# Backplane.net
KiCad netlist of a schematic drawn in Altium Designer
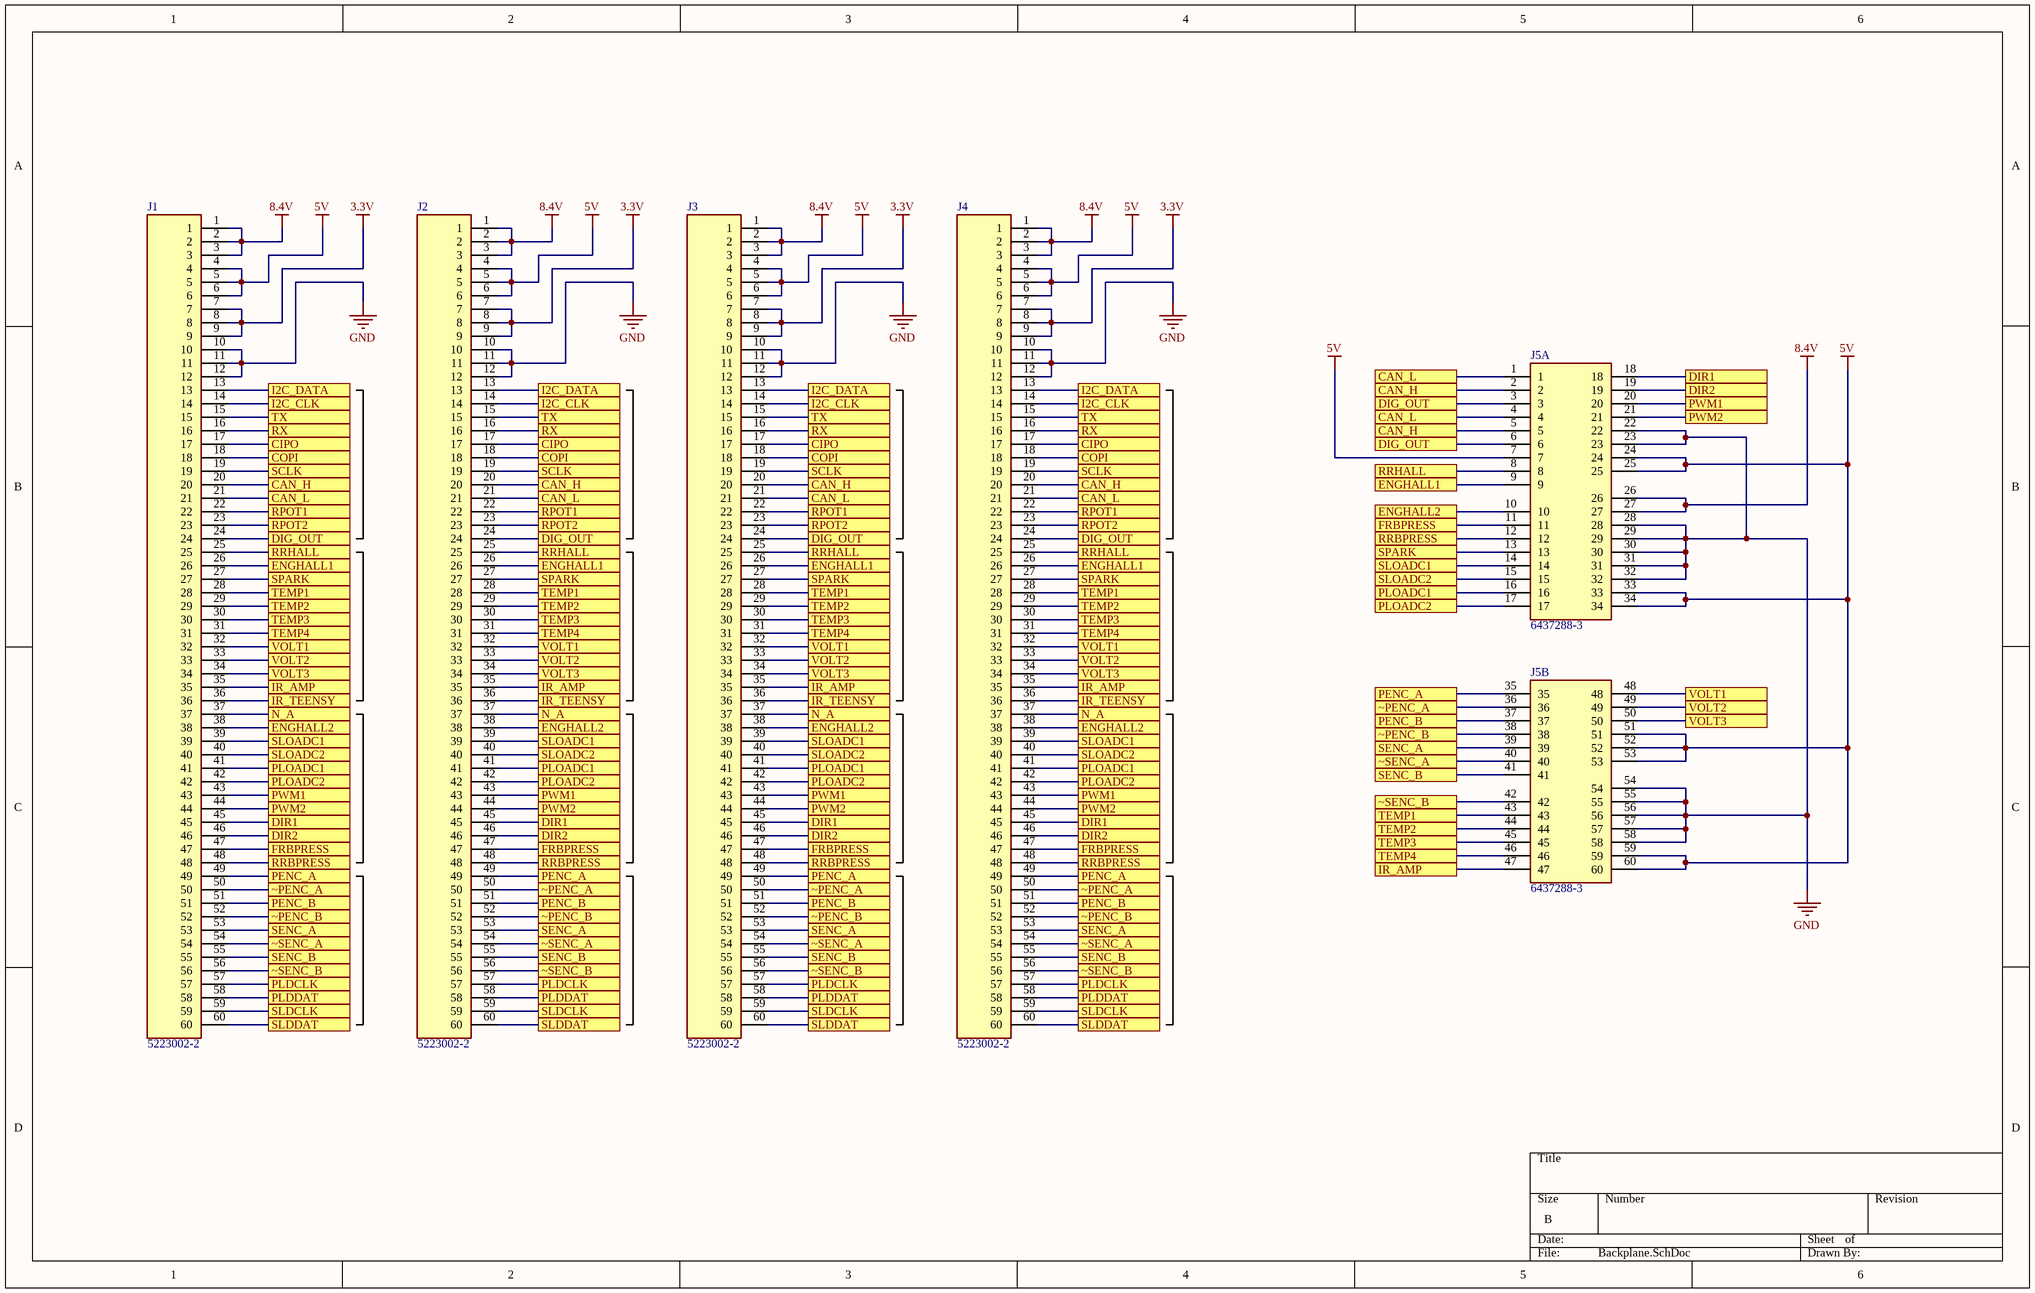
[diagram p0: Backplane.SchDoc]

(export (version "E")
  (design (tool "Eeschema 10.0.6"))
  (components
    (comp (ref "J1")
      (value "5223002-2")
      (footprint "TE_5223002-2")
      (libsource (lib "BoardtoBoardCon") (part "5223002-2"))
    )
    (comp (ref "J2")
      (value "5223002-2")
      (footprint "TE_5223002-2")
      (libsource (lib "BoardtoBoardCon") (part "5223002-2"))
    )
    (comp (ref "J3")
      (value "5223002-2")
      (footprint "TE_5223002-2")
      (libsource (lib "BoardtoBoardCon") (part "5223002-2"))
    )
    (comp (ref "J4")
      (value "5223002-2")
      (footprint "TE_5223002-2")
      (libsource (lib "BoardtoBoardCon") (part "5223002-2"))
    )
    (comp (ref "J5")
      (value "6437288-3")
      (footprint "TE_6437288-3")
      (description "Rectangular Power Connector, Super Seal Series, Through Hole, Receptacle, 60, 1.5 mm, Pin")
      (fields (field (name "MF") "TE Connectivity"))
      (libsource (lib "6437288-3") (part "6437288-3"))
    )
  )
  (nets
    (net (code "1") (name "/CAN_H") (class "Default")
      (node (ref "J1") (pin "20") (pinfunction "20_20") (pintype "passive"))
      (node (ref "J2") (pin "20") (pinfunction "20_20") (pintype "passive"))
      (node (ref "J3") (pin "20") (pinfunction "20_20") (pintype "passive"))
      (node (ref "J4") (pin "20") (pinfunction "20_20") (pintype "passive"))
      (node (ref "J5") (pin "2") (pinfunction "2_2") (pintype "passive"))
      (node (ref "J5") (pin "5") (pinfunction "5_5") (pintype "passive"))
    )
    (net (code "2") (name "/CAN_L") (class "Default")
      (node (ref "J1") (pin "21") (pinfunction "21_21") (pintype "passive"))
      (node (ref "J2") (pin "21") (pinfunction "21_21") (pintype "passive"))
      (node (ref "J3") (pin "21") (pinfunction "21_21") (pintype "passive"))
      (node (ref "J4") (pin "21") (pinfunction "21_21") (pintype "passive"))
      (node (ref "J5") (pin "1") (pinfunction "1_1") (pintype "passive"))
      (node (ref "J5") (pin "4") (pinfunction "4_4") (pintype "passive"))
    )
    (net (code "3") (name "/CIPO") (class "Default")
      (node (ref "J1") (pin "17") (pinfunction "17_17") (pintype "passive"))
      (node (ref "J2") (pin "17") (pinfunction "17_17") (pintype "passive"))
      (node (ref "J3") (pin "17") (pinfunction "17_17") (pintype "passive"))
      (node (ref "J4") (pin "17") (pinfunction "17_17") (pintype "passive"))
    )
    (net (code "4") (name "/COPI") (class "Default")
      (node (ref "J1") (pin "18") (pinfunction "18_18") (pintype "passive"))
      (node (ref "J2") (pin "18") (pinfunction "18_18") (pintype "passive"))
      (node (ref "J3") (pin "18") (pinfunction "18_18") (pintype "passive"))
      (node (ref "J4") (pin "18") (pinfunction "18_18") (pintype "passive"))
    )
    (net (code "5") (name "/DIG_OUT") (class "Default")
      (node (ref "J1") (pin "24") (pinfunction "24_24") (pintype "passive"))
      (node (ref "J2") (pin "24") (pinfunction "24_24") (pintype "passive"))
      (node (ref "J3") (pin "24") (pinfunction "24_24") (pintype "passive"))
      (node (ref "J4") (pin "24") (pinfunction "24_24") (pintype "passive"))
      (node (ref "J5") (pin "3") (pinfunction "3_3") (pintype "passive"))
      (node (ref "J5") (pin "6") (pinfunction "6_6") (pintype "passive"))
    )
    (net (code "6") (name "/DIR1") (class "Default")
      (node (ref "J1") (pin "45") (pinfunction "45_45") (pintype "passive"))
      (node (ref "J2") (pin "45") (pinfunction "45_45") (pintype "passive"))
      (node (ref "J3") (pin "45") (pinfunction "45_45") (pintype "passive"))
      (node (ref "J4") (pin "45") (pinfunction "45_45") (pintype "passive"))
      (node (ref "J5") (pin "18") (pinfunction "18_18") (pintype "passive"))
    )
    (net (code "7") (name "/DIR2") (class "Default")
      (node (ref "J1") (pin "46") (pinfunction "46_46") (pintype "passive"))
      (node (ref "J2") (pin "46") (pinfunction "46_46") (pintype "passive"))
      (node (ref "J3") (pin "46") (pinfunction "46_46") (pintype "passive"))
      (node (ref "J4") (pin "46") (pinfunction "46_46") (pintype "passive"))
      (node (ref "J5") (pin "19") (pinfunction "19_19") (pintype "passive"))
    )
    (net (code "8") (name "/ENGHALL1") (class "Default")
      (node (ref "J1") (pin "26") (pinfunction "26_26") (pintype "passive"))
      (node (ref "J2") (pin "26") (pinfunction "26_26") (pintype "passive"))
      (node (ref "J3") (pin "26") (pinfunction "26_26") (pintype "passive"))
      (node (ref "J4") (pin "26") (pinfunction "26_26") (pintype "passive"))
      (node (ref "J5") (pin "9") (pinfunction "9_9") (pintype "passive"))
    )
    (net (code "9") (name "/ENGHALL2") (class "Default")
      (node (ref "J1") (pin "38") (pinfunction "38_38") (pintype "passive"))
      (node (ref "J2") (pin "38") (pinfunction "38_38") (pintype "passive"))
      (node (ref "J3") (pin "38") (pinfunction "38_38") (pintype "passive"))
      (node (ref "J4") (pin "38") (pinfunction "38_38") (pintype "passive"))
      (node (ref "J5") (pin "10") (pinfunction "10_10") (pintype "passive"))
    )
    (net (code "10") (name "/FRBPRESS") (class "Default")
      (node (ref "J1") (pin "47") (pinfunction "47_47") (pintype "passive"))
      (node (ref "J2") (pin "47") (pinfunction "47_47") (pintype "passive"))
      (node (ref "J3") (pin "47") (pinfunction "47_47") (pintype "passive"))
      (node (ref "J4") (pin "47") (pinfunction "47_47") (pintype "passive"))
      (node (ref "J5") (pin "11") (pinfunction "11_11") (pintype "passive"))
    )
    (net (code "11") (name "/I2C_CLK") (class "Default")
      (node (ref "J1") (pin "14") (pinfunction "14_14") (pintype "passive"))
      (node (ref "J2") (pin "14") (pinfunction "14_14") (pintype "passive"))
      (node (ref "J3") (pin "14") (pinfunction "14_14") (pintype "passive"))
      (node (ref "J4") (pin "14") (pinfunction "14_14") (pintype "passive"))
    )
    (net (code "12") (name "/I2C_DATA") (class "Default")
      (node (ref "J1") (pin "13") (pinfunction "13_13") (pintype "passive"))
      (node (ref "J2") (pin "13") (pinfunction "13_13") (pintype "passive"))
      (node (ref "J3") (pin "13") (pinfunction "13_13") (pintype "passive"))
      (node (ref "J4") (pin "13") (pinfunction "13_13") (pintype "passive"))
    )
    (net (code "13") (name "/IR_AMP") (class "Default")
      (node (ref "J1") (pin "35") (pinfunction "35_35") (pintype "passive"))
      (node (ref "J2") (pin "35") (pinfunction "35_35") (pintype "passive"))
      (node (ref "J3") (pin "35") (pinfunction "35_35") (pintype "passive"))
      (node (ref "J4") (pin "35") (pinfunction "35_35") (pintype "passive"))
      (node (ref "J5") (pin "47") (pinfunction "47_47") (pintype "passive"))
    )
    (net (code "14") (name "/IR_TEENSY") (class "Default")
      (node (ref "J1") (pin "36") (pinfunction "36_36") (pintype "passive"))
      (node (ref "J2") (pin "36") (pinfunction "36_36") (pintype "passive"))
      (node (ref "J3") (pin "36") (pinfunction "36_36") (pintype "passive"))
      (node (ref "J4") (pin "36") (pinfunction "36_36") (pintype "passive"))
    )
    (net (code "15") (name "/N_A") (class "Default")
      (node (ref "J1") (pin "37") (pinfunction "37_37") (pintype "passive"))
      (node (ref "J2") (pin "37") (pinfunction "37_37") (pintype "passive"))
      (node (ref "J3") (pin "37") (pinfunction "37_37") (pintype "passive"))
      (node (ref "J4") (pin "37") (pinfunction "37_37") (pintype "passive"))
    )
    (net (code "16") (name "/PENC_A") (class "Default")
      (node (ref "J1") (pin "49") (pinfunction "49_49") (pintype "passive"))
      (node (ref "J2") (pin "49") (pinfunction "49_49") (pintype "passive"))
      (node (ref "J3") (pin "49") (pinfunction "49_49") (pintype "passive"))
      (node (ref "J4") (pin "49") (pinfunction "49_49") (pintype "passive"))
      (node (ref "J5") (pin "35") (pinfunction "35_35") (pintype "passive"))
    )
    (net (code "17") (name "/PENC_B") (class "Default")
      (node (ref "J1") (pin "51") (pinfunction "51_51") (pintype "passive"))
      (node (ref "J2") (pin "51") (pinfunction "51_51") (pintype "passive"))
      (node (ref "J3") (pin "51") (pinfunction "51_51") (pintype "passive"))
      (node (ref "J4") (pin "51") (pinfunction "51_51") (pintype "passive"))
      (node (ref "J5") (pin "37") (pinfunction "37_37") (pintype "passive"))
    )
    (net (code "18") (name "/PLDCLK") (class "Default")
      (node (ref "J1") (pin "57") (pinfunction "57_57") (pintype "passive"))
      (node (ref "J2") (pin "57") (pinfunction "57_57") (pintype "passive"))
      (node (ref "J3") (pin "57") (pinfunction "57_57") (pintype "passive"))
      (node (ref "J4") (pin "57") (pinfunction "57_57") (pintype "passive"))
    )
    (net (code "19") (name "/PLDDAT") (class "Default")
      (node (ref "J1") (pin "58") (pinfunction "58_58") (pintype "passive"))
      (node (ref "J2") (pin "58") (pinfunction "58_58") (pintype "passive"))
      (node (ref "J3") (pin "58") (pinfunction "58_58") (pintype "passive"))
      (node (ref "J4") (pin "58") (pinfunction "58_58") (pintype "passive"))
    )
    (net (code "20") (name "/PLOADC1") (class "Default")
      (node (ref "J1") (pin "41") (pinfunction "41_41") (pintype "passive"))
      (node (ref "J2") (pin "41") (pinfunction "41_41") (pintype "passive"))
      (node (ref "J3") (pin "41") (pinfunction "41_41") (pintype "passive"))
      (node (ref "J4") (pin "41") (pinfunction "41_41") (pintype "passive"))
      (node (ref "J5") (pin "16") (pinfunction "16_16") (pintype "passive"))
    )
    (net (code "21") (name "/PLOADC2") (class "Default")
      (node (ref "J1") (pin "42") (pinfunction "42_42") (pintype "passive"))
      (node (ref "J2") (pin "42") (pinfunction "42_42") (pintype "passive"))
      (node (ref "J3") (pin "42") (pinfunction "42_42") (pintype "passive"))
      (node (ref "J4") (pin "42") (pinfunction "42_42") (pintype "passive"))
      (node (ref "J5") (pin "17") (pinfunction "17_17") (pintype "passive"))
    )
    (net (code "22") (name "/PWM1") (class "Default")
      (node (ref "J1") (pin "43") (pinfunction "43_43") (pintype "passive"))
      (node (ref "J2") (pin "43") (pinfunction "43_43") (pintype "passive"))
      (node (ref "J3") (pin "43") (pinfunction "43_43") (pintype "passive"))
      (node (ref "J4") (pin "43") (pinfunction "43_43") (pintype "passive"))
      (node (ref "J5") (pin "20") (pinfunction "20_20") (pintype "passive"))
    )
    (net (code "23") (name "/PWM2") (class "Default")
      (node (ref "J1") (pin "44") (pinfunction "44_44") (pintype "passive"))
      (node (ref "J2") (pin "44") (pinfunction "44_44") (pintype "passive"))
      (node (ref "J3") (pin "44") (pinfunction "44_44") (pintype "passive"))
      (node (ref "J4") (pin "44") (pinfunction "44_44") (pintype "passive"))
      (node (ref "J5") (pin "21") (pinfunction "21_21") (pintype "passive"))
    )
    (net (code "24") (name "/RPOT1") (class "Default")
      (node (ref "J1") (pin "22") (pinfunction "22_22") (pintype "passive"))
      (node (ref "J2") (pin "22") (pinfunction "22_22") (pintype "passive"))
      (node (ref "J3") (pin "22") (pinfunction "22_22") (pintype "passive"))
      (node (ref "J4") (pin "22") (pinfunction "22_22") (pintype "passive"))
    )
    (net (code "25") (name "/RPOT2") (class "Default")
      (node (ref "J1") (pin "23") (pinfunction "23_23") (pintype "passive"))
      (node (ref "J2") (pin "23") (pinfunction "23_23") (pintype "passive"))
      (node (ref "J3") (pin "23") (pinfunction "23_23") (pintype "passive"))
      (node (ref "J4") (pin "23") (pinfunction "23_23") (pintype "passive"))
    )
    (net (code "26") (name "/RRBPRESS") (class "Default")
      (node (ref "J1") (pin "48") (pinfunction "48_48") (pintype "passive"))
      (node (ref "J2") (pin "48") (pinfunction "48_48") (pintype "passive"))
      (node (ref "J3") (pin "48") (pinfunction "48_48") (pintype "passive"))
      (node (ref "J4") (pin "48") (pinfunction "48_48") (pintype "passive"))
      (node (ref "J5") (pin "12") (pinfunction "12_12") (pintype "passive"))
    )
    (net (code "27") (name "/RRHALL") (class "Default")
      (node (ref "J1") (pin "25") (pinfunction "25_25") (pintype "passive"))
      (node (ref "J2") (pin "25") (pinfunction "25_25") (pintype "passive"))
      (node (ref "J3") (pin "25") (pinfunction "25_25") (pintype "passive"))
      (node (ref "J4") (pin "25") (pinfunction "25_25") (pintype "passive"))
      (node (ref "J5") (pin "8") (pinfunction "8_8") (pintype "passive"))
    )
    (net (code "28") (name "/RX") (class "Default")
      (node (ref "J1") (pin "16") (pinfunction "16_16") (pintype "passive"))
      (node (ref "J2") (pin "16") (pinfunction "16_16") (pintype "passive"))
      (node (ref "J3") (pin "16") (pinfunction "16_16") (pintype "passive"))
      (node (ref "J4") (pin "16") (pinfunction "16_16") (pintype "passive"))
    )
    (net (code "29") (name "/SCLK") (class "Default")
      (node (ref "J1") (pin "19") (pinfunction "19_19") (pintype "passive"))
      (node (ref "J2") (pin "19") (pinfunction "19_19") (pintype "passive"))
      (node (ref "J3") (pin "19") (pinfunction "19_19") (pintype "passive"))
      (node (ref "J4") (pin "19") (pinfunction "19_19") (pintype "passive"))
    )
    (net (code "30") (name "/SENC_A") (class "Default")
      (node (ref "J1") (pin "53") (pinfunction "53_53") (pintype "passive"))
      (node (ref "J2") (pin "53") (pinfunction "53_53") (pintype "passive"))
      (node (ref "J3") (pin "53") (pinfunction "53_53") (pintype "passive"))
      (node (ref "J4") (pin "53") (pinfunction "53_53") (pintype "passive"))
      (node (ref "J5") (pin "39") (pinfunction "39_39") (pintype "passive"))
    )
    (net (code "31") (name "/SENC_B") (class "Default")
      (node (ref "J1") (pin "55") (pinfunction "55_55") (pintype "passive"))
      (node (ref "J2") (pin "55") (pinfunction "55_55") (pintype "passive"))
      (node (ref "J3") (pin "55") (pinfunction "55_55") (pintype "passive"))
      (node (ref "J4") (pin "55") (pinfunction "55_55") (pintype "passive"))
      (node (ref "J5") (pin "41") (pinfunction "41_41") (pintype "passive"))
    )
    (net (code "32") (name "/SLDCLK") (class "Default")
      (node (ref "J1") (pin "59") (pinfunction "59_59") (pintype "passive"))
      (node (ref "J2") (pin "59") (pinfunction "59_59") (pintype "passive"))
      (node (ref "J3") (pin "59") (pinfunction "59_59") (pintype "passive"))
      (node (ref "J4") (pin "59") (pinfunction "59_59") (pintype "passive"))
    )
    (net (code "33") (name "/SLDDAT") (class "Default")
      (node (ref "J1") (pin "60") (pinfunction "60_60") (pintype "passive"))
      (node (ref "J2") (pin "60") (pinfunction "60_60") (pintype "passive"))
      (node (ref "J3") (pin "60") (pinfunction "60_60") (pintype "passive"))
      (node (ref "J4") (pin "60") (pinfunction "60_60") (pintype "passive"))
    )
    (net (code "34") (name "/SLOADC1") (class "Default")
      (node (ref "J1") (pin "39") (pinfunction "39_39") (pintype "passive"))
      (node (ref "J2") (pin "39") (pinfunction "39_39") (pintype "passive"))
      (node (ref "J3") (pin "39") (pinfunction "39_39") (pintype "passive"))
      (node (ref "J4") (pin "39") (pinfunction "39_39") (pintype "passive"))
      (node (ref "J5") (pin "14") (pinfunction "14_14") (pintype "passive"))
    )
    (net (code "35") (name "/SLOADC2") (class "Default")
      (node (ref "J1") (pin "40") (pinfunction "40_40") (pintype "passive"))
      (node (ref "J2") (pin "40") (pinfunction "40_40") (pintype "passive"))
      (node (ref "J3") (pin "40") (pinfunction "40_40") (pintype "passive"))
      (node (ref "J4") (pin "40") (pinfunction "40_40") (pintype "passive"))
      (node (ref "J5") (pin "15") (pinfunction "15_15") (pintype "passive"))
    )
    (net (code "36") (name "/SPARK") (class "Default")
      (node (ref "J1") (pin "27") (pinfunction "27_27") (pintype "passive"))
      (node (ref "J2") (pin "27") (pinfunction "27_27") (pintype "passive"))
      (node (ref "J3") (pin "27") (pinfunction "27_27") (pintype "passive"))
      (node (ref "J4") (pin "27") (pinfunction "27_27") (pintype "passive"))
      (node (ref "J5") (pin "13") (pinfunction "13_13") (pintype "passive"))
    )
    (net (code "37") (name "/TEMP1") (class "Default")
      (node (ref "J1") (pin "28") (pinfunction "28_28") (pintype "passive"))
      (node (ref "J2") (pin "28") (pinfunction "28_28") (pintype "passive"))
      (node (ref "J3") (pin "28") (pinfunction "28_28") (pintype "passive"))
      (node (ref "J4") (pin "28") (pinfunction "28_28") (pintype "passive"))
      (node (ref "J5") (pin "43") (pinfunction "43_43") (pintype "passive"))
    )
    (net (code "38") (name "/TEMP2") (class "Default")
      (node (ref "J1") (pin "29") (pinfunction "29_29") (pintype "passive"))
      (node (ref "J2") (pin "29") (pinfunction "29_29") (pintype "passive"))
      (node (ref "J3") (pin "29") (pinfunction "29_29") (pintype "passive"))
      (node (ref "J4") (pin "29") (pinfunction "29_29") (pintype "passive"))
      (node (ref "J5") (pin "44") (pinfunction "44_44") (pintype "passive"))
    )
    (net (code "39") (name "/TEMP3") (class "Default")
      (node (ref "J1") (pin "30") (pinfunction "30_30") (pintype "passive"))
      (node (ref "J2") (pin "30") (pinfunction "30_30") (pintype "passive"))
      (node (ref "J3") (pin "30") (pinfunction "30_30") (pintype "passive"))
      (node (ref "J4") (pin "30") (pinfunction "30_30") (pintype "passive"))
      (node (ref "J5") (pin "45") (pinfunction "45_45") (pintype "passive"))
    )
    (net (code "40") (name "/TEMP4") (class "Default")
      (node (ref "J1") (pin "31") (pinfunction "31_31") (pintype "passive"))
      (node (ref "J2") (pin "31") (pinfunction "31_31") (pintype "passive"))
      (node (ref "J3") (pin "31") (pinfunction "31_31") (pintype "passive"))
      (node (ref "J4") (pin "31") (pinfunction "31_31") (pintype "passive"))
      (node (ref "J5") (pin "46") (pinfunction "46_46") (pintype "passive"))
    )
    (net (code "41") (name "/TX") (class "Default")
      (node (ref "J1") (pin "15") (pinfunction "15_15") (pintype "passive"))
      (node (ref "J2") (pin "15") (pinfunction "15_15") (pintype "passive"))
      (node (ref "J3") (pin "15") (pinfunction "15_15") (pintype "passive"))
      (node (ref "J4") (pin "15") (pinfunction "15_15") (pintype "passive"))
    )
    (net (code "42") (name "/VOLT1") (class "Default")
      (node (ref "J1") (pin "32") (pinfunction "32_32") (pintype "passive"))
      (node (ref "J2") (pin "32") (pinfunction "32_32") (pintype "passive"))
      (node (ref "J3") (pin "32") (pinfunction "32_32") (pintype "passive"))
      (node (ref "J4") (pin "32") (pinfunction "32_32") (pintype "passive"))
      (node (ref "J5") (pin "48") (pinfunction "48_48") (pintype "passive"))
    )
    (net (code "43") (name "/VOLT2") (class "Default")
      (node (ref "J1") (pin "33") (pinfunction "33_33") (pintype "passive"))
      (node (ref "J2") (pin "33") (pinfunction "33_33") (pintype "passive"))
      (node (ref "J3") (pin "33") (pinfunction "33_33") (pintype "passive"))
      (node (ref "J4") (pin "33") (pinfunction "33_33") (pintype "passive"))
      (node (ref "J5") (pin "49") (pinfunction "49_49") (pintype "passive"))
    )
    (net (code "44") (name "/VOLT3") (class "Default")
      (node (ref "J1") (pin "34") (pinfunction "34_34") (pintype "passive"))
      (node (ref "J2") (pin "34") (pinfunction "34_34") (pintype "passive"))
      (node (ref "J3") (pin "34") (pinfunction "34_34") (pintype "passive"))
      (node (ref "J4") (pin "34") (pinfunction "34_34") (pintype "passive"))
      (node (ref "J5") (pin "50") (pinfunction "50_50") (pintype "passive"))
    )
    (net (code "45") (name "/~PENC_A") (class "Default")
      (node (ref "J1") (pin "50") (pinfunction "50_50") (pintype "passive"))
      (node (ref "J2") (pin "50") (pinfunction "50_50") (pintype "passive"))
      (node (ref "J3") (pin "50") (pinfunction "50_50") (pintype "passive"))
      (node (ref "J4") (pin "50") (pinfunction "50_50") (pintype "passive"))
      (node (ref "J5") (pin "36") (pinfunction "36_36") (pintype "passive"))
    )
    (net (code "46") (name "/~PENC_B") (class "Default")
      (node (ref "J1") (pin "52") (pinfunction "52_52") (pintype "passive"))
      (node (ref "J2") (pin "52") (pinfunction "52_52") (pintype "passive"))
      (node (ref "J3") (pin "52") (pinfunction "52_52") (pintype "passive"))
      (node (ref "J4") (pin "52") (pinfunction "52_52") (pintype "passive"))
      (node (ref "J5") (pin "38") (pinfunction "38_38") (pintype "passive"))
    )
    (net (code "47") (name "/~SENC_A") (class "Default")
      (node (ref "J1") (pin "54") (pinfunction "54_54") (pintype "passive"))
      (node (ref "J2") (pin "54") (pinfunction "54_54") (pintype "passive"))
      (node (ref "J3") (pin "54") (pinfunction "54_54") (pintype "passive"))
      (node (ref "J4") (pin "54") (pinfunction "54_54") (pintype "passive"))
      (node (ref "J5") (pin "40") (pinfunction "40_40") (pintype "passive"))
    )
    (net (code "48") (name "/~SENC_B") (class "Default")
      (node (ref "J1") (pin "56") (pinfunction "56_56") (pintype "passive"))
      (node (ref "J2") (pin "56") (pinfunction "56_56") (pintype "passive"))
      (node (ref "J3") (pin "56") (pinfunction "56_56") (pintype "passive"))
      (node (ref "J4") (pin "56") (pinfunction "56_56") (pintype "passive"))
      (node (ref "J5") (pin "42") (pinfunction "42_42") (pintype "passive"))
    )
    (net (code "49") (name "3.3V") (class "Default")
      (node (ref "J1") (pin "7") (pinfunction "7_7") (pintype "passive"))
      (node (ref "J1") (pin "8") (pinfunction "8_8") (pintype "passive"))
      (node (ref "J1") (pin "9") (pinfunction "9_9") (pintype "passive"))
      (node (ref "J2") (pin "7") (pinfunction "7_7") (pintype "passive"))
      (node (ref "J2") (pin "8") (pinfunction "8_8") (pintype "passive"))
      (node (ref "J2") (pin "9") (pinfunction "9_9") (pintype "passive"))
      (node (ref "J3") (pin "7") (pinfunction "7_7") (pintype "passive"))
      (node (ref "J3") (pin "8") (pinfunction "8_8") (pintype "passive"))
      (node (ref "J3") (pin "9") (pinfunction "9_9") (pintype "passive"))
      (node (ref "J4") (pin "7") (pinfunction "7_7") (pintype "passive"))
      (node (ref "J4") (pin "8") (pinfunction "8_8") (pintype "passive"))
      (node (ref "J4") (pin "9") (pinfunction "9_9") (pintype "passive"))
    )
    (net (code "50") (name "5V") (class "Default")
      (node (ref "J1") (pin "4") (pinfunction "4_4") (pintype "passive"))
      (node (ref "J1") (pin "5") (pinfunction "5_5") (pintype "passive"))
      (node (ref "J1") (pin "6") (pinfunction "6_6") (pintype "passive"))
      (node (ref "J2") (pin "4") (pinfunction "4_4") (pintype "passive"))
      (node (ref "J2") (pin "5") (pinfunction "5_5") (pintype "passive"))
      (node (ref "J2") (pin "6") (pinfunction "6_6") (pintype "passive"))
      (node (ref "J3") (pin "4") (pinfunction "4_4") (pintype "passive"))
      (node (ref "J3") (pin "5") (pinfunction "5_5") (pintype "passive"))
      (node (ref "J3") (pin "6") (pinfunction "6_6") (pintype "passive"))
      (node (ref "J4") (pin "4") (pinfunction "4_4") (pintype "passive"))
      (node (ref "J4") (pin "5") (pinfunction "5_5") (pintype "passive"))
      (node (ref "J4") (pin "6") (pinfunction "6_6") (pintype "passive"))
      (node (ref "J5") (pin "24") (pinfunction "24_24") (pintype "passive"))
      (node (ref "J5") (pin "25") (pinfunction "25_25") (pintype "passive"))
      (node (ref "J5") (pin "33") (pinfunction "33_33") (pintype "passive"))
      (node (ref "J5") (pin "34") (pinfunction "34_34") (pintype "passive"))
      (node (ref "J5") (pin "51") (pinfunction "51_51") (pintype "passive"))
      (node (ref "J5") (pin "52") (pinfunction "52_52") (pintype "passive"))
      (node (ref "J5") (pin "53") (pinfunction "53_53") (pintype "passive"))
      (node (ref "J5") (pin "59") (pinfunction "59_59") (pintype "passive"))
      (node (ref "J5") (pin "60") (pinfunction "60_60") (pintype "passive"))
      (node (ref "J5") (pin "7") (pinfunction "7_7") (pintype "passive"))
    )
    (net (code "51") (name "8.4V") (class "Default")
      (node (ref "J1") (pin "1") (pinfunction "1_1") (pintype "passive"))
      (node (ref "J1") (pin "2") (pinfunction "2_2") (pintype "passive"))
      (node (ref "J1") (pin "3") (pinfunction "3_3") (pintype "passive"))
      (node (ref "J2") (pin "1") (pinfunction "1_1") (pintype "passive"))
      (node (ref "J2") (pin "2") (pinfunction "2_2") (pintype "passive"))
      (node (ref "J2") (pin "3") (pinfunction "3_3") (pintype "passive"))
      (node (ref "J3") (pin "1") (pinfunction "1_1") (pintype "passive"))
      (node (ref "J3") (pin "2") (pinfunction "2_2") (pintype "passive"))
      (node (ref "J3") (pin "3") (pinfunction "3_3") (pintype "passive"))
      (node (ref "J4") (pin "1") (pinfunction "1_1") (pintype "passive"))
      (node (ref "J4") (pin "2") (pinfunction "2_2") (pintype "passive"))
      (node (ref "J4") (pin "3") (pinfunction "3_3") (pintype "passive"))
      (node (ref "J5") (pin "26") (pinfunction "26_26") (pintype "passive"))
      (node (ref "J5") (pin "27") (pinfunction "27_27") (pintype "passive"))
    )
    (net (code "52") (name "GND") (class "Default")
      (node (ref "J1") (pin "10") (pinfunction "10_10") (pintype "passive"))
      (node (ref "J1") (pin "11") (pinfunction "11_11") (pintype "passive"))
      (node (ref "J1") (pin "12") (pinfunction "12_12") (pintype "passive"))
      (node (ref "J2") (pin "10") (pinfunction "10_10") (pintype "passive"))
      (node (ref "J2") (pin "11") (pinfunction "11_11") (pintype "passive"))
      (node (ref "J2") (pin "12") (pinfunction "12_12") (pintype "passive"))
      (node (ref "J3") (pin "10") (pinfunction "10_10") (pintype "passive"))
      (node (ref "J3") (pin "11") (pinfunction "11_11") (pintype "passive"))
      (node (ref "J3") (pin "12") (pinfunction "12_12") (pintype "passive"))
      (node (ref "J4") (pin "10") (pinfunction "10_10") (pintype "passive"))
      (node (ref "J4") (pin "11") (pinfunction "11_11") (pintype "passive"))
      (node (ref "J4") (pin "12") (pinfunction "12_12") (pintype "passive"))
      (node (ref "J5") (pin "22") (pinfunction "22_22") (pintype "passive"))
      (node (ref "J5") (pin "23") (pinfunction "23_23") (pintype "passive"))
      (node (ref "J5") (pin "28") (pinfunction "28_28") (pintype "passive"))
      (node (ref "J5") (pin "29") (pinfunction "29_29") (pintype "passive"))
      (node (ref "J5") (pin "30") (pinfunction "30_30") (pintype "passive"))
      (node (ref "J5") (pin "31") (pinfunction "31_31") (pintype "passive"))
      (node (ref "J5") (pin "32") (pinfunction "32_32") (pintype "passive"))
      (node (ref "J5") (pin "54") (pinfunction "54_54") (pintype "passive"))
      (node (ref "J5") (pin "55") (pinfunction "55_55") (pintype "passive"))
      (node (ref "J5") (pin "56") (pinfunction "56_56") (pintype "passive"))
      (node (ref "J5") (pin "57") (pinfunction "57_57") (pintype "passive"))
      (node (ref "J5") (pin "58") (pinfunction "58_58") (pintype "passive"))
    )
  )
)
